# 04_LMS7002M_Digital.net
KiCad netlist of a schematic drawn in Altium Designer
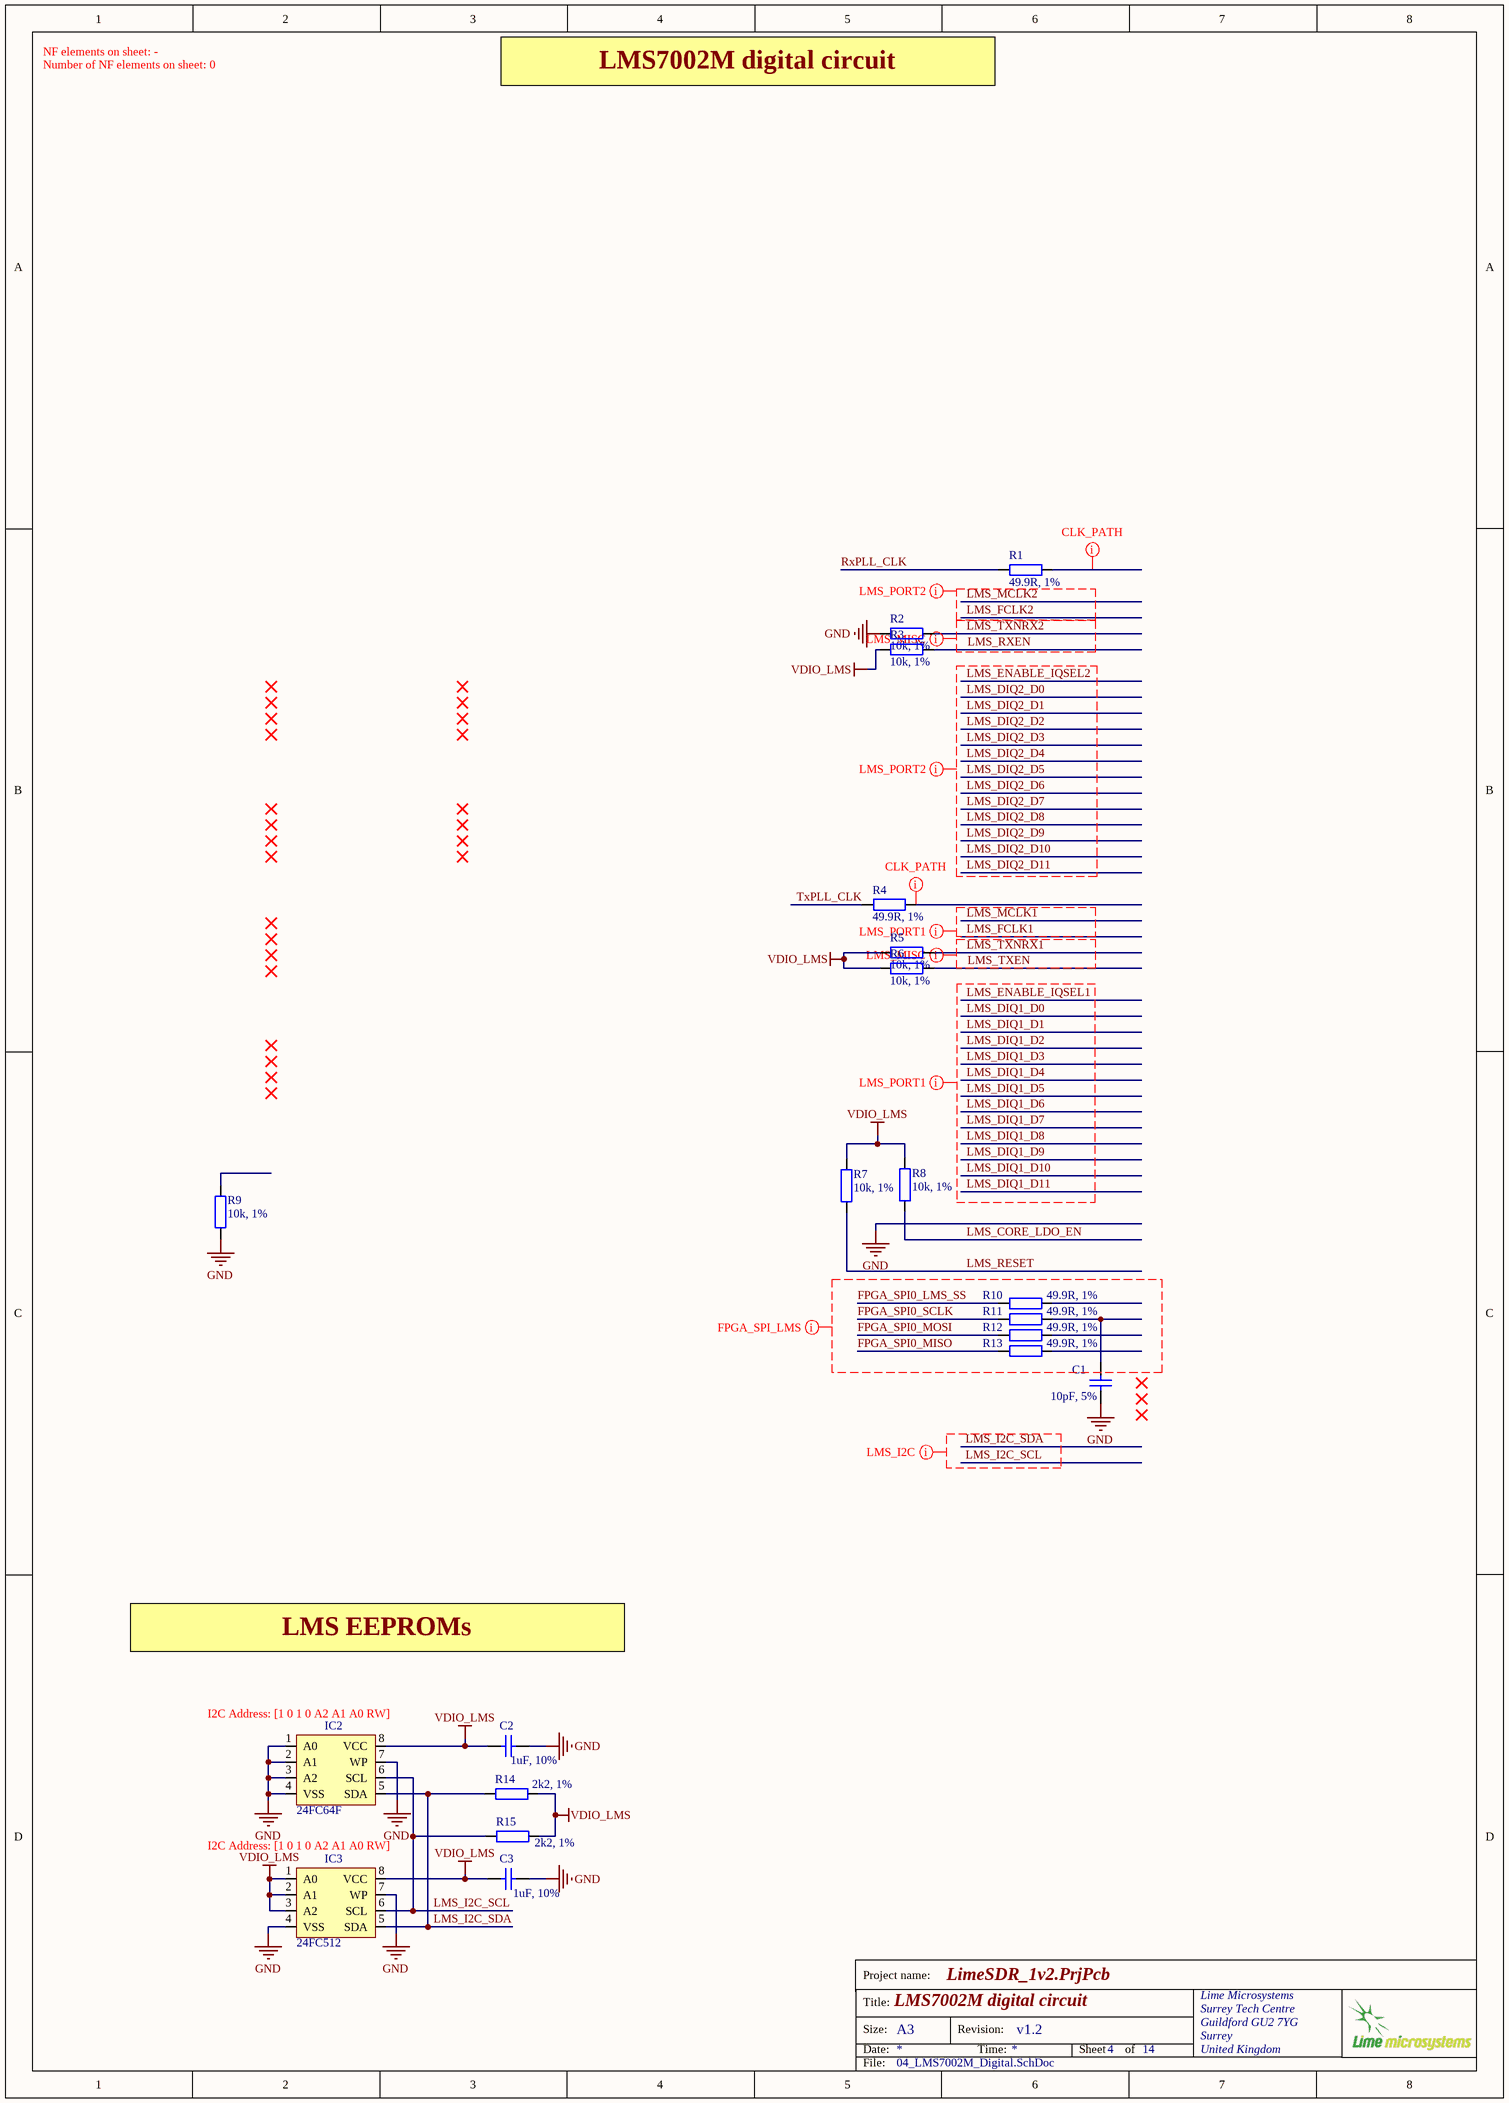
[diagram p0: 04_LMS7002M_Digital.SchDoc]

(export (version "E")
  (design (tool "Eeschema 10.0.6"))
  (components
    (comp (ref "C1")
      (value "10pF, 5%")
      (footprint "CAP0402")
      (fields (field (name "MANUFACTURER") "AVX"))
      (libsource (lib "LimeMicroAltiumLib_schLib") (part "Cap_0402"))
    )
    (comp (ref "C2")
      (value "1uF, 10%")
      (footprint "CAP0402")
      (fields (field (name "MANUFACTURER") "TDK"))
      (libsource (lib "LimeMicroAltiumLib_schLib") (part "Cap_0402"))
    )
    (comp (ref "C3")
      (value "1uF, 10%")
      (footprint "CAP0402")
      (fields (field (name "MANUFACTURER") "TDK"))
      (libsource (lib "LimeMicroAltiumLib_schLib") (part "Cap_0402"))
    )
    (comp (ref "IC2")
      (value "24FC64F")
      (footprint "24FC512")
      (fields (field (name "MANUFACTURER") "Microchip Technology"))
      (libsource (lib "LimeMicroAltiumLib_schLib") (part "24FC64F"))
    )
    (comp (ref "IC3")
      (value "24FC512")
      (footprint "24FC512")
      (fields (field (name "MANUFACTURER") "Microchip Technology"))
      (libsource (lib "LimeMicroAltiumLib_schLib") (part "24FC512"))
    )
    (comp (ref "R1")
      (value "49.9R, 1%")
      (footprint "LimeMicroAltiumLib_pcbLib:RES0402")
      (fields
        (field (name "TOLERANCE") "±1%")
        (field (name "MANUFACTURER") "Samsung Electro-Mechanics America, Inc.")
        (field (name "MANUFACTURER PART NUMBER") "RC1005F49R9CS")
      )
      (libsource (lib "LimeMicroAltiumLib_schLib") (part "Res_0402"))
    )
    (comp (ref "R2")
      (value "10k, 1%")
      (footprint "RES0402")
      (fields (field (name "MANUFACTURER") "Yageo") (field (name "TOLERANCE") "±1%"))
      (libsource (lib "LimeMicroAltiumLib_schLib") (part "Res_0402"))
    )
    (comp (ref "R3")
      (value "10k, 1%")
      (footprint "RES0402")
      (fields (field (name "MANUFACTURER") "Yageo") (field (name "TOLERANCE") "±1%"))
      (libsource (lib "LimeMicroAltiumLib_schLib") (part "Res_0402"))
    )
    (comp (ref "R4")
      (value "49.9R, 1%")
      (footprint "LimeMicroAltiumLib_pcbLib:RES0402")
      (fields
        (field (name "TOLERANCE") "±1%")
        (field (name "MANUFACTURER") "Samsung Electro-Mechanics America, Inc.")
        (field (name "MANUFACTURER PART NUMBER") "RC1005F49R9CS")
      )
      (libsource (lib "LimeMicroAltiumLib_schLib") (part "Res_0402"))
    )
    (comp (ref "R5")
      (value "10k, 1%")
      (footprint "RES0402")
      (fields (field (name "MANUFACTURER") "Yageo") (field (name "TOLERANCE") "±1%"))
      (libsource (lib "LimeMicroAltiumLib_schLib") (part "Res_0402"))
    )
    (comp (ref "R6")
      (value "10k, 1%")
      (footprint "RES0402")
      (fields (field (name "MANUFACTURER") "Yageo") (field (name "TOLERANCE") "±1%"))
      (libsource (lib "LimeMicroAltiumLib_schLib") (part "Res_0402"))
    )
    (comp (ref "R7")
      (value "10k, 1%")
      (footprint "RES0402")
      (fields (field (name "MANUFACTURER") "Yageo") (field (name "TOLERANCE") "±1%"))
      (libsource (lib "LimeMicroAltiumLib_schLib") (part "Res_0402"))
    )
    (comp (ref "R8")
      (value "10k, 1%")
      (footprint "RES0402")
      (fields (field (name "MANUFACTURER") "Yageo") (field (name "TOLERANCE") "±1%"))
      (libsource (lib "LimeMicroAltiumLib_schLib") (part "Res_0402"))
    )
    (comp (ref "R9")
      (value "10k, 1%")
      (footprint "RES0402")
      (fields (field (name "MANUFACTURER") "Yageo") (field (name "TOLERANCE") "±1%"))
      (libsource (lib "LimeMicroAltiumLib_schLib") (part "Res_0402"))
    )
    (comp (ref "R10")
      (value "49.9R, 1%")
      (footprint "LimeMicroAltiumLib_pcbLib:RES0402")
      (fields
        (field (name "TOLERANCE") "±1%")
        (field (name "MANUFACTURER") "Samsung Electro-Mechanics America, Inc.")
        (field (name "MANUFACTURER PART NUMBER") "RC1005F49R9CS")
      )
      (libsource (lib "LimeMicroAltiumLib_schLib") (part "Res_0402"))
    )
    (comp (ref "R11")
      (value "49.9R, 1%")
      (footprint "LimeMicroAltiumLib_pcbLib:RES0402")
      (fields
        (field (name "TOLERANCE") "±1%")
        (field (name "MANUFACTURER") "Samsung Electro-Mechanics America, Inc.")
        (field (name "MANUFACTURER PART NUMBER") "RC1005F49R9CS")
      )
      (libsource (lib "LimeMicroAltiumLib_schLib") (part "Res_0402"))
    )
    (comp (ref "R12")
      (value "49.9R, 1%")
      (footprint "LimeMicroAltiumLib_pcbLib:RES0402")
      (fields
        (field (name "TOLERANCE") "±1%")
        (field (name "MANUFACTURER") "Samsung Electro-Mechanics America, Inc.")
        (field (name "MANUFACTURER PART NUMBER") "RC1005F49R9CS")
      )
      (libsource (lib "LimeMicroAltiumLib_schLib") (part "Res_0402"))
    )
    (comp (ref "R13")
      (value "49.9R, 1%")
      (footprint "LimeMicroAltiumLib_pcbLib:RES0402")
      (fields
        (field (name "TOLERANCE") "±1%")
        (field (name "MANUFACTURER") "Samsung Electro-Mechanics America, Inc.")
        (field (name "MANUFACTURER PART NUMBER") "RC1005F49R9CS")
      )
      (libsource (lib "LimeMicroAltiumLib_schLib") (part "Res_0402"))
    )
    (comp (ref "R14")
      (value "2k2, 1%")
      (footprint "RES0402")
      (fields (field (name "MANUFACTURER") "Stackpole Electronics Inc") (field (name "TOLERANCE") "±1%"))
      (libsource (lib "LimeMicroAltiumLib_schLib") (part "Res_0402"))
    )
    (comp (ref "R15")
      (value "2k2, 1%")
      (footprint "RES0402")
      (fields (field (name "MANUFACTURER") "Stackpole Electronics Inc") (field (name "TOLERANCE") "±1%"))
      (libsource (lib "LimeMicroAltiumLib_schLib") (part "Res_0402"))
    )
  )
  (nets
    (net (code "1") (name "/FPGA_SPI0_LMS_SS") (class "Default")
      (node (ref "R10") (pin "2") (pinfunction "2_2") (pintype "passive"))
    )
    (net (code "2") (name "/FPGA_SPI0_MISO") (class "Default")
      (node (ref "R13") (pin "2") (pinfunction "2_2") (pintype "passive"))
    )
    (net (code "3") (name "/FPGA_SPI0_MOSI") (class "Default")
      (node (ref "R12") (pin "2") (pinfunction "2_2") (pintype "passive"))
    )
    (net (code "4") (name "/FPGA_SPI0_SCLK") (class "Default")
      (node (ref "R11") (pin "2") (pinfunction "2_2") (pintype "passive"))
    )
    (net (code "5") (name "/LMS_CORE_LDO_EN") (class "Default")
      (node (ref "R8") (pin "1") (pinfunction "1_1") (pintype "passive"))
    )
    (net (code "34") (name "/LMS_I2C_SCL") (class "Default")
      (node (ref "IC2") (pin "6") (pinfunction "SCL_6") (pintype "passive"))
      (node (ref "IC3") (pin "6") (pinfunction "SCL_6") (pintype "passive"))
      (node (ref "R15") (pin "2") (pinfunction "2_2") (pintype "passive"))
    )
    (net (code "35") (name "/LMS_I2C_SDA") (class "Default")
      (node (ref "IC2") (pin "5") (pinfunction "SDA_5") (pintype "passive"))
      (node (ref "IC3") (pin "5") (pinfunction "SDA_5") (pintype "passive"))
      (node (ref "R14") (pin "2") (pinfunction "2_2") (pintype "passive"))
    )
    (net (code "38") (name "/LMS_RESET") (class "Default")
      (node (ref "R7") (pin "1") (pinfunction "1_1") (pintype "passive"))
    )
    (net (code "39") (name "/LMS_RXEN") (class "Default")
      (node (ref "R3") (pin "2") (pinfunction "2_2") (pintype "passive"))
    )
    (net (code "40") (name "/LMS_TXEN") (class "Default")
      (node (ref "R6") (pin "2") (pinfunction "2_2") (pintype "passive"))
    )
    (net (code "41") (name "/LMS_TXNRX1") (class "Default")
      (node (ref "R5") (pin "2") (pinfunction "2_2") (pintype "passive"))
    )
    (net (code "42") (name "/LMS_TXNRX2") (class "Default")
      (node (ref "R2") (pin "2") (pinfunction "2_2") (pintype "passive"))
    )
    (net (code "43") (name "/RxPLL_CLK") (class "Default")
      (node (ref "R1") (pin "2") (pinfunction "2_2") (pintype "passive"))
    )
    (net (code "44") (name "/TxPLL_CLK") (class "Default")
      (node (ref "R4") (pin "2") (pinfunction "2_2") (pintype "passive"))
    )
    (net (code "45") (name "GND") (class "Default")
      (node (ref "C1") (pin "2") (pinfunction "2_2") (pintype "passive"))
      (node (ref "C2") (pin "1") (pinfunction "1_1") (pintype "passive"))
      (node (ref "C3") (pin "1") (pinfunction "1_1") (pintype "passive"))
      (node (ref "IC2") (pin "1") (pinfunction "A0_1") (pintype "passive"))
      (node (ref "IC2") (pin "2") (pinfunction "A1_2") (pintype "passive"))
      (node (ref "IC2") (pin "3") (pinfunction "A2_3") (pintype "passive"))
      (node (ref "IC2") (pin "4") (pinfunction "VSS_4") (pintype "passive"))
      (node (ref "IC2") (pin "7") (pinfunction "WP_7") (pintype "passive"))
      (node (ref "IC3") (pin "4") (pinfunction "VSS_4") (pintype "passive"))
      (node (ref "IC3") (pin "7") (pinfunction "WP_7") (pintype "passive"))
      (node (ref "R2") (pin "1") (pinfunction "1_1") (pintype "passive"))
      (node (ref "R9") (pin "2") (pinfunction "2_2") (pintype "passive"))
    )
    (net (code "46") (name "Net-(C1-Pad1)") (class "Default")
      (node (ref "C1") (pin "1") (pinfunction "1_1") (pintype "passive"))
      (node (ref "R11") (pin "1") (pinfunction "1_1") (pintype "passive"))
    )
    (net (code "47") (name "VDIO_LMS") (class "Default")
      (node (ref "C2") (pin "2") (pinfunction "2_2") (pintype "passive"))
      (node (ref "C3") (pin "2") (pinfunction "2_2") (pintype "passive"))
      (node (ref "IC2") (pin "8") (pinfunction "VCC_8") (pintype "passive"))
      (node (ref "IC3") (pin "1") (pinfunction "A0_1") (pintype "passive"))
      (node (ref "IC3") (pin "2") (pinfunction "A1_2") (pintype "passive"))
      (node (ref "IC3") (pin "3") (pinfunction "A2_3") (pintype "passive"))
      (node (ref "IC3") (pin "8") (pinfunction "VCC_8") (pintype "passive"))
      (node (ref "R14") (pin "1") (pinfunction "1_1") (pintype "passive"))
      (node (ref "R15") (pin "1") (pinfunction "1_1") (pintype "passive"))
      (node (ref "R3") (pin "1") (pinfunction "1_1") (pintype "passive"))
      (node (ref "R5") (pin "1") (pinfunction "1_1") (pintype "passive"))
      (node (ref "R6") (pin "1") (pinfunction "1_1") (pintype "passive"))
      (node (ref "R7") (pin "2") (pinfunction "2_2") (pintype "passive"))
      (node (ref "R8") (pin "2") (pinfunction "2_2") (pintype "passive"))
    )
    (net (code "48") (name "unconnected-(R1-Pad1)") (class "Default")
      (node (ref "R1") (pin "1") (pinfunction "1_1") (pintype "passive"))
    )
    (net (code "49") (name "unconnected-(R4-Pad1)") (class "Default")
      (node (ref "R4") (pin "1") (pinfunction "1_1") (pintype "passive"))
    )
    (net (code "50") (name "unconnected-(R9-Pad1)") (class "Default")
      (node (ref "R9") (pin "1") (pinfunction "1_1") (pintype "passive"))
    )
    (net (code "51") (name "unconnected-(R10-Pad1)") (class "Default")
      (node (ref "R10") (pin "1") (pinfunction "1_1") (pintype "passive"))
    )
    (net (code "52") (name "unconnected-(R12-Pad1)") (class "Default")
      (node (ref "R12") (pin "1") (pinfunction "1_1") (pintype "passive"))
    )
    (net (code "53") (name "unconnected-(R13-Pad1)") (class "Default")
      (node (ref "R13") (pin "1") (pinfunction "1_1") (pintype "passive"))
    )
  )
)
